# 4x4CherryExpansion.net
KiCad netlist of a schematic drawn in EAGLE
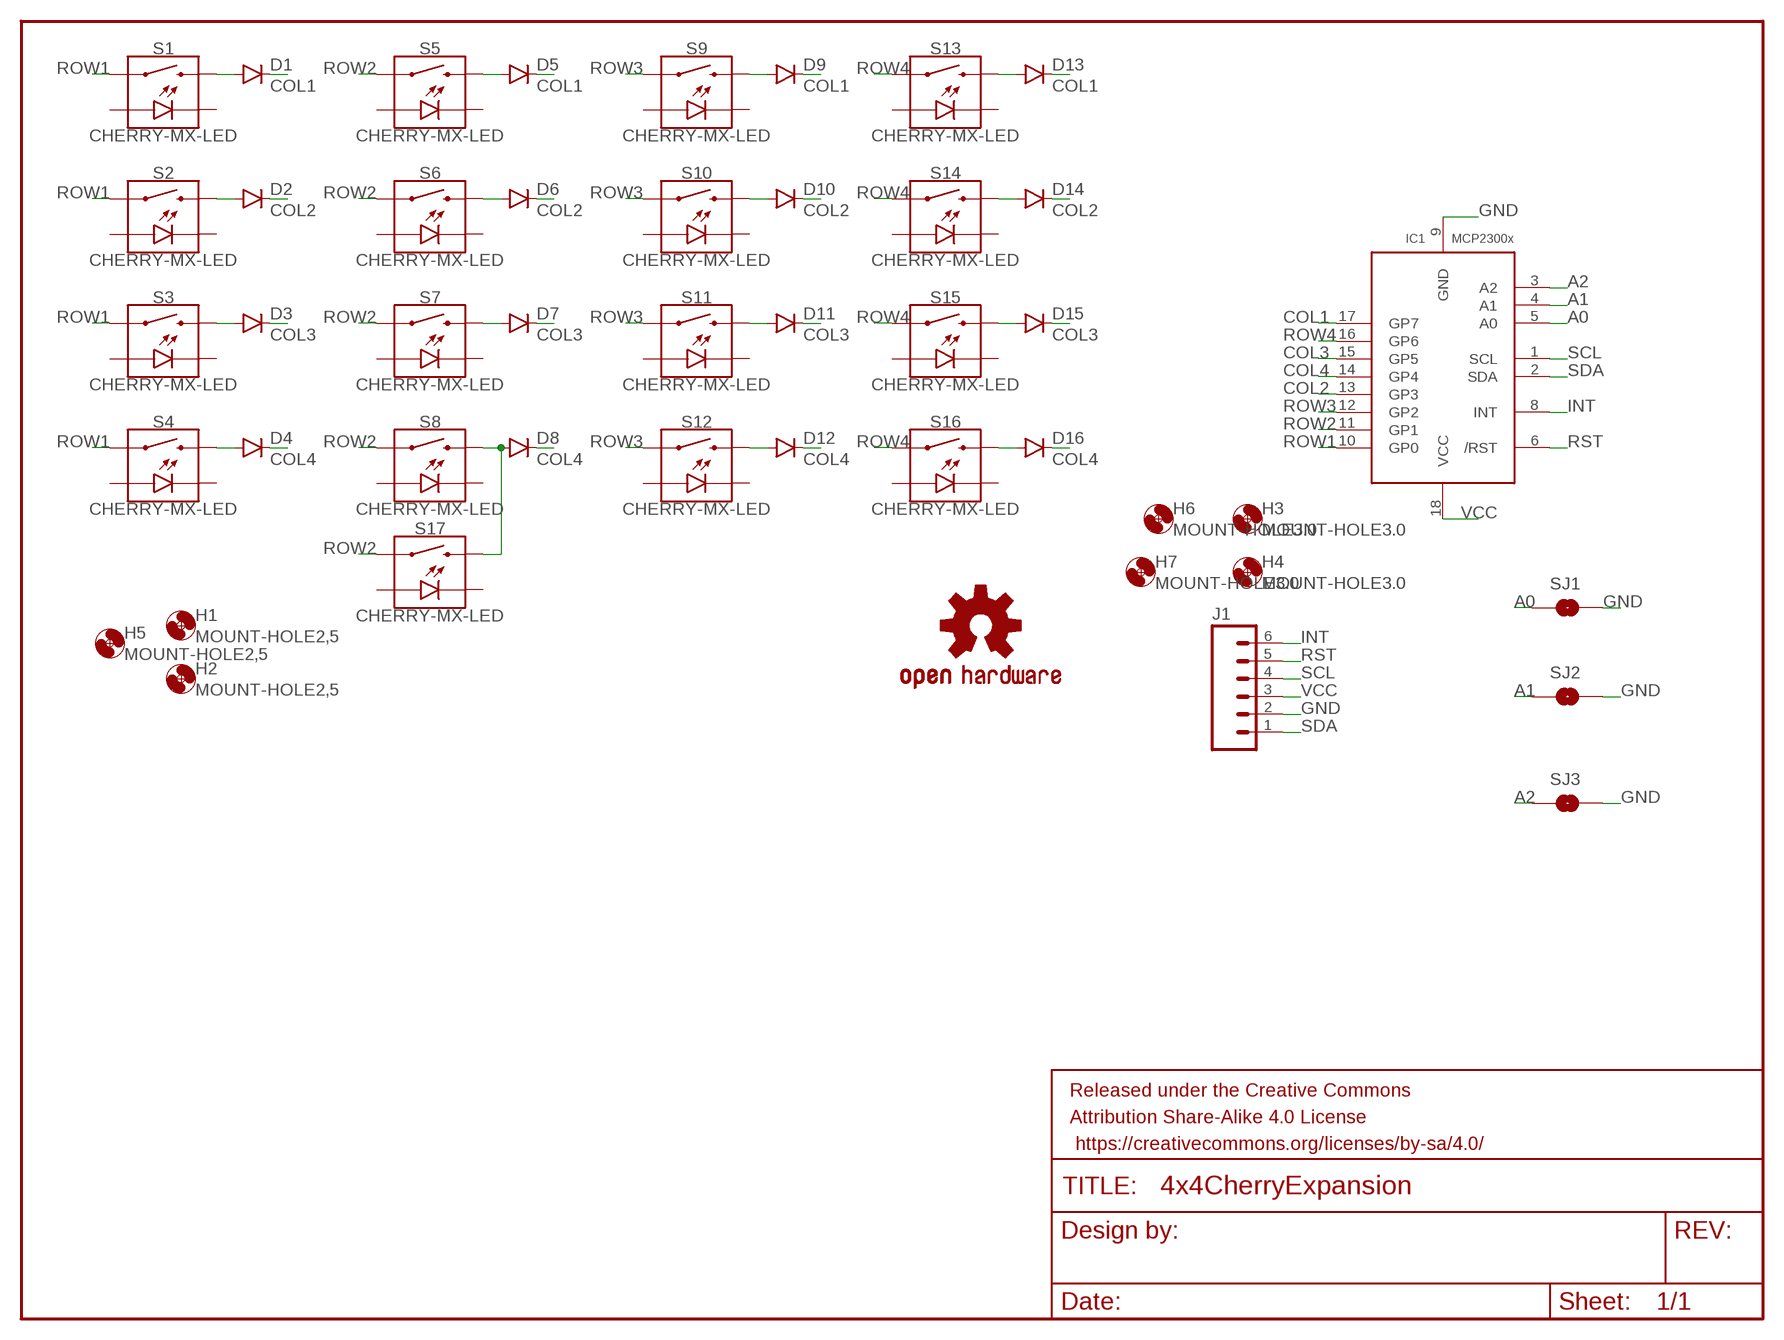
[diagram p0: schematic, sheet 1]

(export (version "E")
  (design (tool "Eeschema 10.0.6"))
  (components
    (comp (ref "D1")
      (value "DIODEPTH")
      (footprint "eagle-import:DIODE-1N4001")
      (libsource (lib "eagle-import") (part "DIODEPTH"))
    )
    (comp (ref "D2")
      (value "DIODEPTH")
      (footprint "eagle-import:DIODE-1N4001")
      (libsource (lib "eagle-import") (part "DIODEPTH"))
    )
    (comp (ref "D3")
      (value "DIODEPTH")
      (footprint "eagle-import:DIODE-1N4001")
      (libsource (lib "eagle-import") (part "DIODEPTH"))
    )
    (comp (ref "D4")
      (value "DIODEPTH")
      (footprint "eagle-import:DIODE-1N4001")
      (libsource (lib "eagle-import") (part "DIODEPTH"))
    )
    (comp (ref "D5")
      (value "DIODEPTH")
      (footprint "eagle-import:DIODE-1N4001")
      (libsource (lib "eagle-import") (part "DIODEPTH"))
    )
    (comp (ref "D6")
      (value "DIODEPTH")
      (footprint "eagle-import:DIODE-1N4001")
      (libsource (lib "eagle-import") (part "DIODEPTH"))
    )
    (comp (ref "D7")
      (value "DIODEPTH")
      (footprint "eagle-import:DIODE-1N4001")
      (libsource (lib "eagle-import") (part "DIODEPTH"))
    )
    (comp (ref "D8")
      (value "DIODEPTH")
      (footprint "eagle-import:DIODE-1N4001")
      (libsource (lib "eagle-import") (part "DIODEPTH"))
    )
    (comp (ref "D9")
      (value "DIODEPTH")
      (footprint "eagle-import:DIODE-1N4001")
      (libsource (lib "eagle-import") (part "DIODEPTH"))
    )
    (comp (ref "D10")
      (value "DIODEPTH")
      (footprint "eagle-import:DIODE-1N4001")
      (libsource (lib "eagle-import") (part "DIODEPTH"))
    )
    (comp (ref "D11")
      (value "DIODEPTH")
      (footprint "eagle-import:DIODE-1N4001")
      (libsource (lib "eagle-import") (part "DIODEPTH"))
    )
    (comp (ref "D12")
      (value "DIODEPTH")
      (footprint "eagle-import:DIODE-1N4001")
      (libsource (lib "eagle-import") (part "DIODEPTH"))
    )
    (comp (ref "D13")
      (value "DIODEPTH")
      (footprint "eagle-import:DIODE-1N4001")
      (libsource (lib "eagle-import") (part "DIODEPTH"))
    )
    (comp (ref "D14")
      (value "DIODEPTH")
      (footprint "eagle-import:DIODE-1N4001")
      (libsource (lib "eagle-import") (part "DIODEPTH"))
    )
    (comp (ref "D15")
      (value "DIODEPTH")
      (footprint "eagle-import:DIODE-1N4001")
      (libsource (lib "eagle-import") (part "DIODEPTH"))
    )
    (comp (ref "D16")
      (value "DIODEPTH")
      (footprint "eagle-import:DIODE-1N4001")
      (libsource (lib "eagle-import") (part "DIODEPTH"))
    )
    (comp (ref "FRAME1")
      (value "FRAME-LETTER")
      (footprint "eagle-import:CREATIVE_COMMONS")
      (libsource (lib "eagle-import") (part "FRAME-LETTER"))
    )
    (comp (ref "H1")
      (value "MOUNT-HOLE2,5")
      (footprint "eagle-import:2,8")
      (libsource (lib "eagle-import") (part "MOUNT-HOLE2,5"))
    )
    (comp (ref "H2")
      (value "MOUNT-HOLE2,5")
      (footprint "eagle-import:2,8")
      (libsource (lib "eagle-import") (part "MOUNT-HOLE2,5"))
    )
    (comp (ref "H3")
      (value "MOUNT-HOLE3.0")
      (footprint "eagle-import:3,0")
      (libsource (lib "eagle-import") (part "MOUNT-HOLE3.0"))
    )
    (comp (ref "H4")
      (value "MOUNT-HOLE3.0")
      (footprint "eagle-import:3,0")
      (libsource (lib "eagle-import") (part "MOUNT-HOLE3.0"))
    )
    (comp (ref "H5")
      (value "MOUNT-HOLE2,5")
      (footprint "eagle-import:2,8")
      (libsource (lib "eagle-import") (part "MOUNT-HOLE2,5"))
    )
    (comp (ref "H6")
      (value "MOUNT-HOLE3.0")
      (footprint "eagle-import:3,0")
      (libsource (lib "eagle-import") (part "MOUNT-HOLE3.0"))
    )
    (comp (ref "H7")
      (value "MOUNT-HOLE3.0")
      (footprint "eagle-import:3,0")
      (libsource (lib "eagle-import") (part "MOUNT-HOLE3.0"))
    )
    (comp (ref "IC1")
      (value "MCP23008/P")
      (footprint "eagle-import:DIL18")
      (libsource (lib "eagle-import") (part "MCP23008/P"))
    )
    (comp (ref "J1")
      (value "M06SILK_FEMALE_PTH")
      (footprint "eagle-import:1X06")
      (libsource (lib "eagle-import") (part "M06SILK_FEMALE_PTH"))
    )
    (comp (ref "LOGO1")
      (value "OSHW-LOGOL")
      (footprint "eagle-import:OSHW-LOGO-L")
      (libsource (lib "eagle-import") (part "OSHW-LOGOL"))
    )
    (comp (ref "S1")
      (value "CHERRY-MX-LED")
      (footprint "eagle-import:CHERRY-MX-LED")
      (libsource (lib "eagle-import") (part "CHERRY-MX-LED"))
    )
    (comp (ref "S2")
      (value "CHERRY-MX-LED")
      (footprint "eagle-import:CHERRY-MX-LED")
      (libsource (lib "eagle-import") (part "CHERRY-MX-LED"))
    )
    (comp (ref "S3")
      (value "CHERRY-MX-LED")
      (footprint "eagle-import:CHERRY-MX-LED")
      (libsource (lib "eagle-import") (part "CHERRY-MX-LED"))
    )
    (comp (ref "S4")
      (value "CHERRY-MX-LED")
      (footprint "eagle-import:CHERRY-MX-LED")
      (libsource (lib "eagle-import") (part "CHERRY-MX-LED"))
    )
    (comp (ref "S5")
      (value "CHERRY-MX-LED")
      (footprint "eagle-import:CHERRY-MX-LED")
      (libsource (lib "eagle-import") (part "CHERRY-MX-LED"))
    )
    (comp (ref "S6")
      (value "CHERRY-MX-LED")
      (footprint "eagle-import:CHERRY-MX-LED")
      (libsource (lib "eagle-import") (part "CHERRY-MX-LED"))
    )
    (comp (ref "S7")
      (value "CHERRY-MX-LED")
      (footprint "eagle-import:CHERRY-MX-LED")
      (libsource (lib "eagle-import") (part "CHERRY-MX-LED"))
    )
    (comp (ref "S8")
      (value "CHERRY-MX-LED")
      (footprint "eagle-import:CHERRY-MX-LED")
      (libsource (lib "eagle-import") (part "CHERRY-MX-LED"))
    )
    (comp (ref "S9")
      (value "CHERRY-MX-LED")
      (footprint "eagle-import:CHERRY-MX-LED")
      (libsource (lib "eagle-import") (part "CHERRY-MX-LED"))
    )
    (comp (ref "S10")
      (value "CHERRY-MX-LED")
      (footprint "eagle-import:CHERRY-MX-LED")
      (libsource (lib "eagle-import") (part "CHERRY-MX-LED"))
    )
    (comp (ref "S11")
      (value "CHERRY-MX-LED")
      (footprint "eagle-import:CHERRY-MX-LED")
      (libsource (lib "eagle-import") (part "CHERRY-MX-LED"))
    )
    (comp (ref "S12")
      (value "CHERRY-MX-LED")
      (footprint "eagle-import:CHERRY-MX-LED")
      (libsource (lib "eagle-import") (part "CHERRY-MX-LED"))
    )
    (comp (ref "S13")
      (value "CHERRY-MX-LED")
      (footprint "eagle-import:CHERRY-MX-LED")
      (libsource (lib "eagle-import") (part "CHERRY-MX-LED"))
    )
    (comp (ref "S14")
      (value "CHERRY-MX-LED")
      (footprint "eagle-import:CHERRY-MX-LED")
      (libsource (lib "eagle-import") (part "CHERRY-MX-LED"))
    )
    (comp (ref "S15")
      (value "CHERRY-MX-LED")
      (footprint "eagle-import:CHERRY-MX-LED")
      (libsource (lib "eagle-import") (part "CHERRY-MX-LED"))
    )
    (comp (ref "S16")
      (value "CHERRY-MX-LED")
      (footprint "eagle-import:CHERRY-MX-LED")
      (libsource (lib "eagle-import") (part "CHERRY-MX-LED"))
    )
    (comp (ref "S17")
      (value "CHERRY-MX-LED")
      (footprint "eagle-import:CHERRY-MX-LED")
      (libsource (lib "eagle-import") (part "CHERRY-MX-LED"))
    )
    (comp (ref "SJ1")
      (value "SOLDERJUMPERNO")
      (footprint "eagle-import:SJ_2S-NO")
      (libsource (lib "eagle-import") (part "SOLDERJUMPERNO"))
    )
    (comp (ref "SJ2")
      (value "SOLDERJUMPERNO")
      (footprint "eagle-import:SJ_2S-NO")
      (libsource (lib "eagle-import") (part "SOLDERJUMPERNO"))
    )
    (comp (ref "SJ3")
      (value "SOLDERJUMPERNO")
      (footprint "eagle-import:SJ_2S-NO")
      (libsource (lib "eagle-import") (part "SOLDERJUMPERNO"))
    )
  )
  (nets
    (net (code "1") (name "/A0") (class "Default")
      (node (ref "IC1") (pin "5") (pinfunction "A0_5") (pintype "input"))
      (node (ref "SJ1") (pin "1") (pinfunction "1_1") (pintype "passive"))
    )
    (net (code "2") (name "/A1") (class "Default")
      (node (ref "IC1") (pin "4") (pinfunction "A1_4") (pintype "input"))
      (node (ref "SJ2") (pin "1") (pinfunction "1_1") (pintype "passive"))
    )
    (net (code "3") (name "/A2") (class "Default")
      (node (ref "IC1") (pin "3") (pinfunction "A2_3") (pintype "input"))
      (node (ref "SJ3") (pin "1") (pinfunction "1_1") (pintype "passive"))
    )
    (net (code "4") (name "/COL1") (class "Default")
      (node (ref "D1") (pin "C") (pinfunction "C_C") (pintype "passive"))
      (node (ref "D13") (pin "C") (pinfunction "C_C") (pintype "passive"))
      (node (ref "D5") (pin "C") (pinfunction "C_C") (pintype "passive"))
      (node (ref "D9") (pin "C") (pinfunction "C_C") (pintype "passive"))
      (node (ref "IC1") (pin "17") (pinfunction "GP7_17") (pintype "bidirectional"))
    )
    (net (code "5") (name "/COL2") (class "Default")
      (node (ref "D10") (pin "C") (pinfunction "C_C") (pintype "passive"))
      (node (ref "D14") (pin "C") (pinfunction "C_C") (pintype "passive"))
      (node (ref "D2") (pin "C") (pinfunction "C_C") (pintype "passive"))
      (node (ref "D6") (pin "C") (pinfunction "C_C") (pintype "passive"))
      (node (ref "IC1") (pin "13") (pinfunction "GP3_13") (pintype "bidirectional"))
    )
    (net (code "6") (name "/COL3") (class "Default")
      (node (ref "D11") (pin "C") (pinfunction "C_C") (pintype "passive"))
      (node (ref "D15") (pin "C") (pinfunction "C_C") (pintype "passive"))
      (node (ref "D3") (pin "C") (pinfunction "C_C") (pintype "passive"))
      (node (ref "D7") (pin "C") (pinfunction "C_C") (pintype "passive"))
      (node (ref "IC1") (pin "15") (pinfunction "GP5_15") (pintype "bidirectional"))
    )
    (net (code "7") (name "/COL4") (class "Default")
      (node (ref "D12") (pin "C") (pinfunction "C_C") (pintype "passive"))
      (node (ref "D16") (pin "C") (pinfunction "C_C") (pintype "passive"))
      (node (ref "D4") (pin "C") (pinfunction "C_C") (pintype "passive"))
      (node (ref "D8") (pin "C") (pinfunction "C_C") (pintype "passive"))
      (node (ref "IC1") (pin "14") (pinfunction "GP4_14") (pintype "bidirectional"))
    )
    (net (code "8") (name "/GND") (class "Default")
      (node (ref "IC1") (pin "9") (pinfunction "GND_9") (pintype "power_in"))
      (node (ref "J1") (pin "2") (pinfunction "2_2") (pintype "passive"))
      (node (ref "SJ1") (pin "2") (pinfunction "2_2") (pintype "passive"))
      (node (ref "SJ2") (pin "2") (pinfunction "2_2") (pintype "passive"))
      (node (ref "SJ3") (pin "2") (pinfunction "2_2") (pintype "passive"))
    )
    (net (code "9") (name "/INT") (class "Default")
      (node (ref "IC1") (pin "8") (pinfunction "INT_8") (pintype "output"))
      (node (ref "J1") (pin "6") (pinfunction "6_6") (pintype "passive"))
    )
    (net (code "10") (name "/ROW1") (class "Default")
      (node (ref "IC1") (pin "10") (pinfunction "GP0_10") (pintype "bidirectional"))
      (node (ref "S1") (pin "S1") (pinfunction "S1_S1") (pintype "passive"))
      (node (ref "S2") (pin "S1") (pinfunction "S1_S1") (pintype "passive"))
      (node (ref "S3") (pin "S1") (pinfunction "S1_S1") (pintype "passive"))
      (node (ref "S4") (pin "S1") (pinfunction "S1_S1") (pintype "passive"))
    )
    (net (code "11") (name "/ROW2") (class "Default")
      (node (ref "IC1") (pin "11") (pinfunction "GP1_11") (pintype "bidirectional"))
      (node (ref "S17") (pin "S1") (pinfunction "S1_S1") (pintype "passive"))
      (node (ref "S5") (pin "S1") (pinfunction "S1_S1") (pintype "passive"))
      (node (ref "S6") (pin "S1") (pinfunction "S1_S1") (pintype "passive"))
      (node (ref "S7") (pin "S1") (pinfunction "S1_S1") (pintype "passive"))
      (node (ref "S8") (pin "S1") (pinfunction "S1_S1") (pintype "passive"))
    )
    (net (code "12") (name "/ROW3") (class "Default")
      (node (ref "IC1") (pin "12") (pinfunction "GP2_12") (pintype "bidirectional"))
      (node (ref "S10") (pin "S1") (pinfunction "S1_S1") (pintype "passive"))
      (node (ref "S11") (pin "S1") (pinfunction "S1_S1") (pintype "passive"))
      (node (ref "S12") (pin "S1") (pinfunction "S1_S1") (pintype "passive"))
      (node (ref "S9") (pin "S1") (pinfunction "S1_S1") (pintype "passive"))
    )
    (net (code "13") (name "/ROW4") (class "Default")
      (node (ref "IC1") (pin "16") (pinfunction "GP6_16") (pintype "bidirectional"))
      (node (ref "S13") (pin "S1") (pinfunction "S1_S1") (pintype "passive"))
      (node (ref "S14") (pin "S1") (pinfunction "S1_S1") (pintype "passive"))
      (node (ref "S15") (pin "S1") (pinfunction "S1_S1") (pintype "passive"))
      (node (ref "S16") (pin "S1") (pinfunction "S1_S1") (pintype "passive"))
    )
    (net (code "14") (name "/RST") (class "Default")
      (node (ref "IC1") (pin "6") (pinfunction "/RST_6") (pintype "input"))
      (node (ref "J1") (pin "5") (pinfunction "5_5") (pintype "passive"))
    )
    (net (code "15") (name "/SCL") (class "Default")
      (node (ref "IC1") (pin "1") (pinfunction "SCL_1") (pintype "bidirectional"))
      (node (ref "J1") (pin "4") (pinfunction "4_4") (pintype "passive"))
    )
    (net (code "16") (name "/SDA") (class "Default")
      (node (ref "IC1") (pin "2") (pinfunction "SDA_2") (pintype "bidirectional"))
      (node (ref "J1") (pin "1") (pinfunction "1_1") (pintype "passive"))
    )
    (net (code "17") (name "/VCC") (class "Default")
      (node (ref "IC1") (pin "18") (pinfunction "VCC_18") (pintype "power_in"))
      (node (ref "J1") (pin "3") (pinfunction "3_3") (pintype "passive"))
    )
    (net (code "18") (name "Net-(D1-PadA)") (class "Default")
      (node (ref "D1") (pin "A") (pinfunction "A_A") (pintype "passive"))
      (node (ref "S1") (pin "S2") (pinfunction "S2_S2") (pintype "passive"))
    )
    (net (code "19") (name "Net-(D2-PadA)") (class "Default")
      (node (ref "D2") (pin "A") (pinfunction "A_A") (pintype "passive"))
      (node (ref "S2") (pin "S2") (pinfunction "S2_S2") (pintype "passive"))
    )
    (net (code "20") (name "Net-(D3-PadA)") (class "Default")
      (node (ref "D3") (pin "A") (pinfunction "A_A") (pintype "passive"))
      (node (ref "S3") (pin "S2") (pinfunction "S2_S2") (pintype "passive"))
    )
    (net (code "21") (name "Net-(D4-PadA)") (class "Default")
      (node (ref "D4") (pin "A") (pinfunction "A_A") (pintype "passive"))
      (node (ref "S4") (pin "S2") (pinfunction "S2_S2") (pintype "passive"))
    )
    (net (code "22") (name "Net-(D5-PadA)") (class "Default")
      (node (ref "D5") (pin "A") (pinfunction "A_A") (pintype "passive"))
      (node (ref "S5") (pin "S2") (pinfunction "S2_S2") (pintype "passive"))
    )
    (net (code "23") (name "Net-(D6-PadA)") (class "Default")
      (node (ref "D6") (pin "A") (pinfunction "A_A") (pintype "passive"))
      (node (ref "S6") (pin "S2") (pinfunction "S2_S2") (pintype "passive"))
    )
    (net (code "24") (name "Net-(D7-PadA)") (class "Default")
      (node (ref "D7") (pin "A") (pinfunction "A_A") (pintype "passive"))
      (node (ref "S7") (pin "S2") (pinfunction "S2_S2") (pintype "passive"))
    )
    (net (code "25") (name "Net-(D8-PadA)") (class "Default")
      (node (ref "D8") (pin "A") (pinfunction "A_A") (pintype "passive"))
      (node (ref "S17") (pin "S2") (pinfunction "S2_S2") (pintype "passive"))
      (node (ref "S8") (pin "S2") (pinfunction "S2_S2") (pintype "passive"))
    )
    (net (code "26") (name "Net-(D9-PadA)") (class "Default")
      (node (ref "D9") (pin "A") (pinfunction "A_A") (pintype "passive"))
      (node (ref "S9") (pin "S2") (pinfunction "S2_S2") (pintype "passive"))
    )
    (net (code "27") (name "Net-(D10-PadA)") (class "Default")
      (node (ref "D10") (pin "A") (pinfunction "A_A") (pintype "passive"))
      (node (ref "S10") (pin "S2") (pinfunction "S2_S2") (pintype "passive"))
    )
    (net (code "28") (name "Net-(D11-PadA)") (class "Default")
      (node (ref "D11") (pin "A") (pinfunction "A_A") (pintype "passive"))
      (node (ref "S11") (pin "S2") (pinfunction "S2_S2") (pintype "passive"))
    )
    (net (code "29") (name "Net-(D12-PadA)") (class "Default")
      (node (ref "D12") (pin "A") (pinfunction "A_A") (pintype "passive"))
      (node (ref "S12") (pin "S2") (pinfunction "S2_S2") (pintype "passive"))
    )
    (net (code "30") (name "Net-(D13-PadA)") (class "Default")
      (node (ref "D13") (pin "A") (pinfunction "A_A") (pintype "passive"))
      (node (ref "S13") (pin "S2") (pinfunction "S2_S2") (pintype "passive"))
    )
    (net (code "31") (name "Net-(D14-PadA)") (class "Default")
      (node (ref "D14") (pin "A") (pinfunction "A_A") (pintype "passive"))
      (node (ref "S14") (pin "S2") (pinfunction "S2_S2") (pintype "passive"))
    )
    (net (code "32") (name "Net-(D15-PadA)") (class "Default")
      (node (ref "D15") (pin "A") (pinfunction "A_A") (pintype "passive"))
      (node (ref "S15") (pin "S2") (pinfunction "S2_S2") (pintype "passive"))
    )
    (net (code "33") (name "Net-(D16-PadA)") (class "Default")
      (node (ref "D16") (pin "A") (pinfunction "A_A") (pintype "passive"))
      (node (ref "S16") (pin "S2") (pinfunction "S2_S2") (pintype "passive"))
    )
    (net (code "34") (name "unconnected-(S1-C-PadK)") (class "Default")
      (node (ref "S1") (pin "K") (pinfunction "C_K") (pintype "passive"))
    )
    (net (code "35") (name "unconnected-(S1-PadA)") (class "Default")
      (node (ref "S1") (pin "A") (pinfunction "A_A") (pintype "passive"))
    )
    (net (code "36") (name "unconnected-(S2-C-PadK)") (class "Default")
      (node (ref "S2") (pin "K") (pinfunction "C_K") (pintype "passive"))
    )
    (net (code "37") (name "unconnected-(S2-PadA)") (class "Default")
      (node (ref "S2") (pin "A") (pinfunction "A_A") (pintype "passive"))
    )
    (net (code "38") (name "unconnected-(S3-C-PadK)") (class "Default")
      (node (ref "S3") (pin "K") (pinfunction "C_K") (pintype "passive"))
    )
    (net (code "39") (name "unconnected-(S3-PadA)") (class "Default")
      (node (ref "S3") (pin "A") (pinfunction "A_A") (pintype "passive"))
    )
    (net (code "40") (name "unconnected-(S4-C-PadK)") (class "Default")
      (node (ref "S4") (pin "K") (pinfunction "C_K") (pintype "passive"))
    )
    (net (code "41") (name "unconnected-(S4-PadA)") (class "Default")
      (node (ref "S4") (pin "A") (pinfunction "A_A") (pintype "passive"))
    )
    (net (code "42") (name "unconnected-(S5-C-PadK)") (class "Default")
      (node (ref "S5") (pin "K") (pinfunction "C_K") (pintype "passive"))
    )
    (net (code "43") (name "unconnected-(S5-PadA)") (class "Default")
      (node (ref "S5") (pin "A") (pinfunction "A_A") (pintype "passive"))
    )
    (net (code "44") (name "unconnected-(S6-C-PadK)") (class "Default")
      (node (ref "S6") (pin "K") (pinfunction "C_K") (pintype "passive"))
    )
    (net (code "45") (name "unconnected-(S6-PadA)") (class "Default")
      (node (ref "S6") (pin "A") (pinfunction "A_A") (pintype "passive"))
    )
    (net (code "46") (name "unconnected-(S7-C-PadK)") (class "Default")
      (node (ref "S7") (pin "K") (pinfunction "C_K") (pintype "passive"))
    )
    (net (code "47") (name "unconnected-(S7-PadA)") (class "Default")
      (node (ref "S7") (pin "A") (pinfunction "A_A") (pintype "passive"))
    )
    (net (code "48") (name "unconnected-(S8-C-PadK)") (class "Default")
      (node (ref "S8") (pin "K") (pinfunction "C_K") (pintype "passive"))
    )
    (net (code "49") (name "unconnected-(S8-PadA)") (class "Default")
      (node (ref "S8") (pin "A") (pinfunction "A_A") (pintype "passive"))
    )
    (net (code "50") (name "unconnected-(S9-C-PadK)") (class "Default")
      (node (ref "S9") (pin "K") (pinfunction "C_K") (pintype "passive"))
    )
    (net (code "51") (name "unconnected-(S9-PadA)") (class "Default")
      (node (ref "S9") (pin "A") (pinfunction "A_A") (pintype "passive"))
    )
    (net (code "52") (name "unconnected-(S10-C-PadK)") (class "Default")
      (node (ref "S10") (pin "K") (pinfunction "C_K") (pintype "passive"))
    )
    (net (code "53") (name "unconnected-(S10-PadA)") (class "Default")
      (node (ref "S10") (pin "A") (pinfunction "A_A") (pintype "passive"))
    )
    (net (code "54") (name "unconnected-(S11-C-PadK)") (class "Default")
      (node (ref "S11") (pin "K") (pinfunction "C_K") (pintype "passive"))
    )
    (net (code "55") (name "unconnected-(S11-PadA)") (class "Default")
      (node (ref "S11") (pin "A") (pinfunction "A_A") (pintype "passive"))
    )
    (net (code "56") (name "unconnected-(S12-C-PadK)") (class "Default")
      (node (ref "S12") (pin "K") (pinfunction "C_K") (pintype "passive"))
    )
    (net (code "57") (name "unconnected-(S12-PadA)") (class "Default")
      (node (ref "S12") (pin "A") (pinfunction "A_A") (pintype "passive"))
    )
    (net (code "58") (name "unconnected-(S13-C-PadK)") (class "Default")
      (node (ref "S13") (pin "K") (pinfunction "C_K") (pintype "passive"))
    )
    (net (code "59") (name "unconnected-(S13-PadA)") (class "Default")
      (node (ref "S13") (pin "A") (pinfunction "A_A") (pintype "passive"))
    )
    (net (code "60") (name "unconnected-(S14-C-PadK)") (class "Default")
      (node (ref "S14") (pin "K") (pinfunction "C_K") (pintype "passive"))
    )
    (net (code "61") (name "unconnected-(S14-PadA)") (class "Default")
      (node (ref "S14") (pin "A") (pinfunction "A_A") (pintype "passive"))
    )
    (net (code "62") (name "unconnected-(S15-C-PadK)") (class "Default")
      (node (ref "S15") (pin "K") (pinfunction "C_K") (pintype "passive"))
    )
    (net (code "63") (name "unconnected-(S15-PadA)") (class "Default")
      (node (ref "S15") (pin "A") (pinfunction "A_A") (pintype "passive"))
    )
    (net (code "64") (name "unconnected-(S16-C-PadK)") (class "Default")
      (node (ref "S16") (pin "K") (pinfunction "C_K") (pintype "passive"))
    )
    (net (code "65") (name "unconnected-(S16-PadA)") (class "Default")
      (node (ref "S16") (pin "A") (pinfunction "A_A") (pintype "passive"))
    )
    (net (code "66") (name "unconnected-(S17-C-PadK)") (class "Default")
      (node (ref "S17") (pin "K") (pinfunction "C_K") (pintype "passive"))
    )
    (net (code "67") (name "unconnected-(S17-PadA)") (class "Default")
      (node (ref "S17") (pin "A") (pinfunction "A_A") (pintype "passive"))
    )
  )
)
